# charger_schematic.net
KiCad netlist of a schematic drawn in Altium Designer
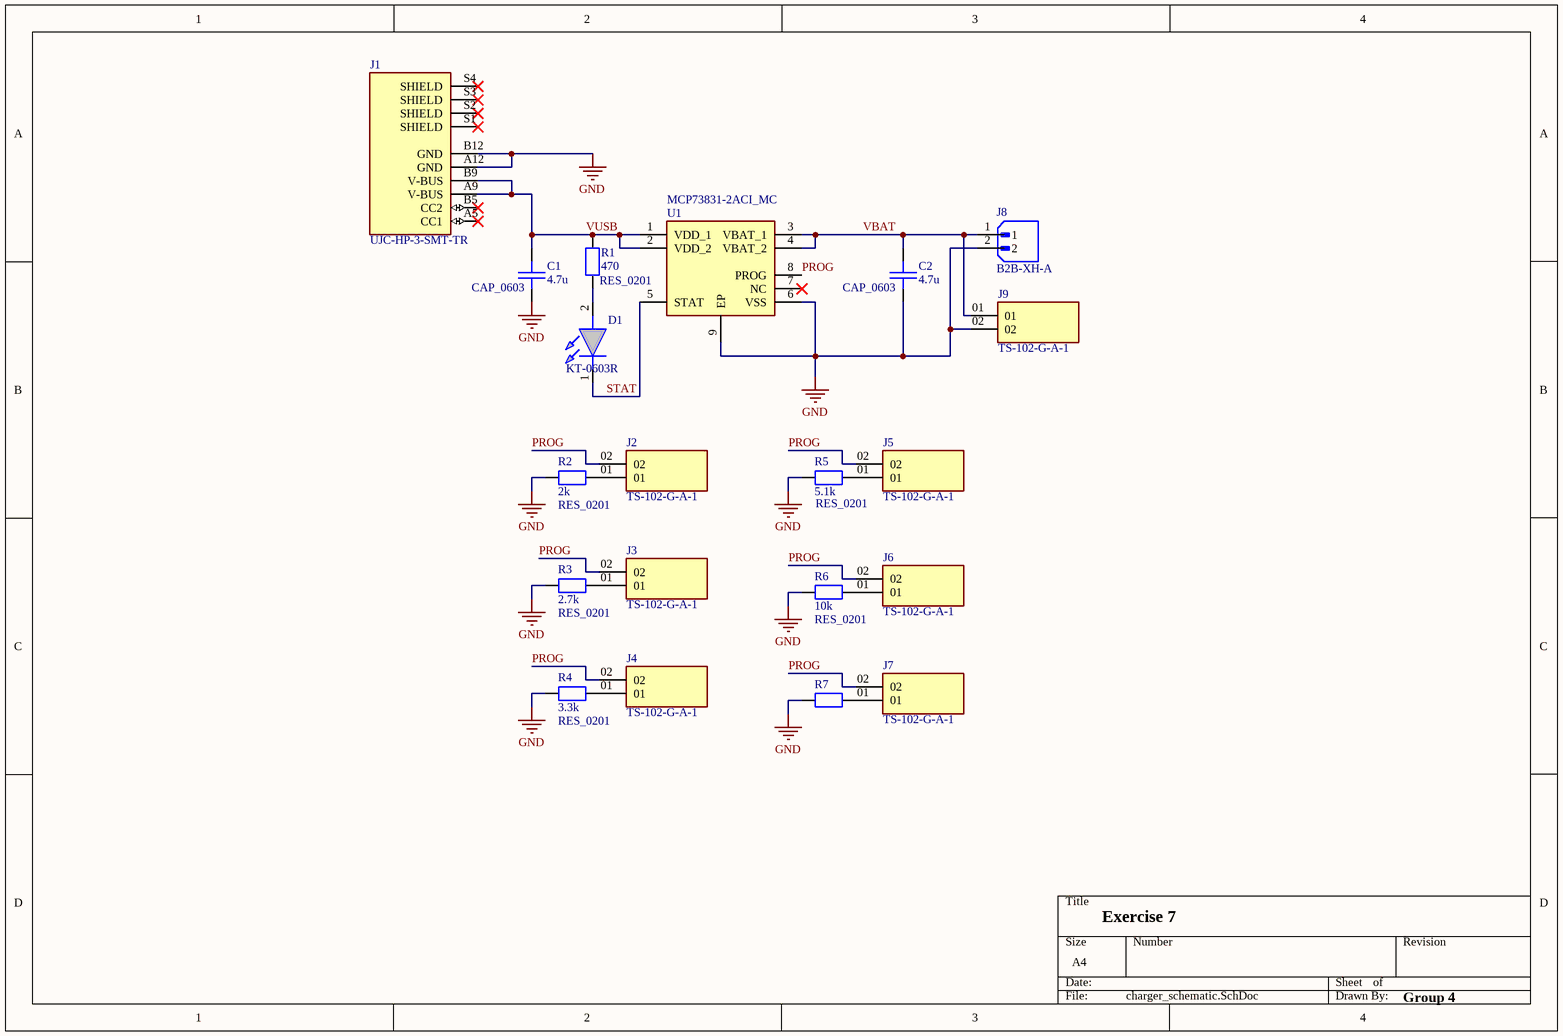
[diagram p0: charger_schematic.SchDoc]

(export (version "E")
  (design (tool "Eeschema 10.0.6"))
  (components
    (comp (ref "C1")
      (value "CAP_0603")
      (footprint "CAP_0603")
      (fields (field (name "ALTIUM_VALUE") "4.7u"))
      (libsource (lib "smd_sch_lib") (part "CAP_0603"))
    )
    (comp (ref "C2")
      (value "CAP_0603")
      (footprint "CAP_0603")
      (fields (field (name "ALTIUM_VALUE") "4.7u"))
      (libsource (lib "smd_sch_lib") (part "CAP_0603"))
    )
    (comp (ref "D1")
      (value "KT-0603R")
      (footprint "LEDC1608X70N")
      (description "Red 615~630nm 1.9~2.2V 0603 Light Emitting Diodes (LED) RoHS")
      (libsource (lib "LED_KT-0603R") (part "KT-0603R"))
    )
    (comp (ref "J1")
      (value "UJC-HP-3-SMT-TR")
      (footprint "CUI_UJC-HP-3-SMT-TR")
      (libsource (lib "UJC-HP-3-SMT-TR") (part "UJC-HP-3-SMT-TR"))
    )
    (comp (ref "J2")
      (value "TS-102-G-A-1")
      (footprint "SAMTEC_TS-102-G-A-1")
      (fields (field (name "MF") "{'manufacturer': u'Samtec Inc.'}"))
      (libsource (lib "TS-102-G-A-1") (part "TS-102-G-A-1"))
    )
    (comp (ref "J3")
      (value "TS-102-G-A-1")
      (footprint "SAMTEC_TS-102-G-A-1")
      (fields (field (name "MF") "{'manufacturer': u'Samtec Inc.'}"))
      (libsource (lib "TS-102-G-A-1") (part "TS-102-G-A-1"))
    )
    (comp (ref "J4")
      (value "TS-102-G-A-1")
      (footprint "SAMTEC_TS-102-G-A-1")
      (fields (field (name "MF") "{'manufacturer': u'Samtec Inc.'}"))
      (libsource (lib "TS-102-G-A-1") (part "TS-102-G-A-1"))
    )
    (comp (ref "J5")
      (value "TS-102-G-A-1")
      (footprint "SAMTEC_TS-102-G-A-1")
      (fields (field (name "MF") "{'manufacturer': u'Samtec Inc.'}"))
      (libsource (lib "TS-102-G-A-1") (part "TS-102-G-A-1"))
    )
    (comp (ref "J6")
      (value "TS-102-G-A-1")
      (footprint "SAMTEC_TS-102-G-A-1")
      (fields (field (name "MF") "{'manufacturer': u'Samtec Inc.'}"))
      (libsource (lib "TS-102-G-A-1") (part "TS-102-G-A-1"))
    )
    (comp (ref "J7")
      (value "TS-102-G-A-1")
      (footprint "SAMTEC_TS-102-G-A-1")
      (fields (field (name "MF") "{'manufacturer': u'Samtec Inc.'}"))
      (libsource (lib "TS-102-G-A-1") (part "TS-102-G-A-1"))
    )
    (comp (ref "J8")
      (value "B2B-XH-A")
      (footprint "JST_B2B-XH-A")
      (fields (field (name "MF") "{'manufacturer': u'JST Sales America Inc.'}"))
      (libsource (lib "B2B-XH-A") (part "B2B-XH-A"))
    )
    (comp (ref "J9")
      (value "TS-102-G-A-1")
      (footprint "SAMTEC_TS-102-G-A-1")
      (fields (field (name "MF") "{'manufacturer': u'Samtec Inc.'}"))
      (libsource (lib "") (part "TS-102-G-A-1_1"))
    )
    (comp (ref "R1")
      (value "RES_0201")
      (footprint "RES_0201")
      (fields (field (name "ALTIUM_VALUE") "470"))
      (libsource (lib "smd_sch_lib") (part "RES_0201"))
    )
    (comp (ref "R2")
      (value "RES_0201")
      (footprint "RES_0201")
      (fields (field (name "ALTIUM_VALUE") "2k"))
      (libsource (lib "smd_sch_lib") (part "RES_0201"))
    )
    (comp (ref "R3")
      (value "RES_0201")
      (footprint "RES_0201")
      (fields (field (name "ALTIUM_VALUE") "2.7k"))
      (libsource (lib "smd_sch_lib") (part "RES_0201"))
    )
    (comp (ref "R4")
      (value "RES_0201")
      (footprint "RES_0201")
      (fields (field (name "ALTIUM_VALUE") "3.3k"))
      (libsource (lib "smd_sch_lib") (part "RES_0201"))
    )
    (comp (ref "R5")
      (value "RES_0201")
      (footprint "RES_0201")
      (fields (field (name "ALTIUM_VALUE") "5.1k"))
      (libsource (lib "smd_sch_lib") (part "RES_0201"))
    )
    (comp (ref "R6")
      (value "RES_0201")
      (footprint "RES_0201")
      (fields (field (name "ALTIUM_VALUE") "10k"))
      (libsource (lib "smd_sch_lib") (part "RES_0201"))
    )
    (comp (ref "R7")
      (value "~")
      (footprint "PCBComponent_1")
      (libsource (lib "res_tht_sym_lib") (part "R_THT"))
    )
    (comp (ref "U1")
      (value "MCP73831-2ACI_MC")
      (footprint "SON50P300X200X100-9N-D")
      (description "Microchip MCP73831-2ACI/MC, Battery Charge Controller Lithium-Ion, Lithium-Polymer, 8-pin DFN")
      (fields
        (field (name "MANUFACTURER_PART_NUMBER") "MCP73831-2ACI/MC")
        (field (name "MOUSER PART NUMBER") "579-MCP73831-2ACI/MC")
      )
      (libsource (lib "MCP73831-2ACI_MC") (part "MCP73831-2ACI_MC"))
    )
  )
  (nets
    (net (code "1") (name "/PROG") (class "Default")
      (node (ref "J2") (pin "02") (pinfunction "02_02") (pintype "passive"))
      (node (ref "J3") (pin "02") (pinfunction "02_02") (pintype "passive"))
      (node (ref "J4") (pin "02") (pinfunction "02_02") (pintype "passive"))
      (node (ref "J5") (pin "02") (pinfunction "02_02") (pintype "passive"))
      (node (ref "J6") (pin "02") (pinfunction "02_02") (pintype "passive"))
      (node (ref "J7") (pin "02") (pinfunction "02_02") (pintype "passive"))
      (node (ref "U1") (pin "8") (pinfunction "PROG_8") (pintype "passive"))
    )
    (net (code "2") (name "/STAT") (class "Default")
      (node (ref "D1") (pin "1") (pinfunction "K_1") (pintype "passive"))
      (node (ref "U1") (pin "5") (pinfunction "STAT_5") (pintype "passive"))
    )
    (net (code "3") (name "/VBAT") (class "Default")
      (node (ref "C2") (pin "2") (pintype "passive"))
      (node (ref "J8") (pin "1") (pinfunction "1_1") (pintype "passive"))
      (node (ref "J9") (pin "01") (pinfunction "01_01") (pintype "passive"))
      (node (ref "U1") (pin "3") (pinfunction "VBAT_1_3") (pintype "passive"))
      (node (ref "U1") (pin "4") (pinfunction "VBAT_2_4") (pintype "passive"))
    )
    (net (code "4") (name "/VUSB") (class "Default")
      (node (ref "C1") (pin "2") (pintype "passive"))
      (node (ref "J1") (pin "A9") (pinfunction "V-BUS_A9") (pintype "power_in"))
      (node (ref "J1") (pin "B9") (pinfunction "V-BUS_B9") (pintype "power_in"))
      (node (ref "R1") (pin "2") (pintype "passive"))
      (node (ref "U1") (pin "1") (pinfunction "VDD_1_1") (pintype "passive"))
      (node (ref "U1") (pin "2") (pinfunction "VDD_2_2") (pintype "passive"))
    )
    (net (code "5") (name "GND") (class "Default")
      (node (ref "C1") (pin "1") (pintype "passive"))
      (node (ref "C2") (pin "1") (pintype "passive"))
      (node (ref "J1") (pin "A12") (pinfunction "GND_A12") (pintype "power_in"))
      (node (ref "J1") (pin "B12") (pinfunction "GND_B12") (pintype "power_in"))
      (node (ref "J8") (pin "2") (pinfunction "2_2") (pintype "passive"))
      (node (ref "J9") (pin "02") (pinfunction "02_02") (pintype "passive"))
      (node (ref "R2") (pin "2") (pintype "passive"))
      (node (ref "R3") (pin "2") (pintype "passive"))
      (node (ref "R4") (pin "2") (pintype "passive"))
      (node (ref "R5") (pin "2") (pintype "passive"))
      (node (ref "R6") (pin "2") (pintype "passive"))
      (node (ref "R7") (pin "2") (pinfunction "2_2") (pintype "passive"))
      (node (ref "U1") (pin "6") (pinfunction "VSS_6") (pintype "passive"))
      (node (ref "U1") (pin "9") (pinfunction "EP_9") (pintype "passive"))
    )
    (net (code "6") (name "Net-(D1-A)") (class "Default")
      (node (ref "D1") (pin "2") (pinfunction "A_2") (pintype "passive"))
      (node (ref "R1") (pin "1") (pintype "passive"))
    )
    (net (code "7") (name "Net-(J2-Pad01)") (class "Default")
      (node (ref "J2") (pin "01") (pinfunction "01_01") (pintype "passive"))
      (node (ref "R2") (pin "1") (pintype "passive"))
    )
    (net (code "8") (name "Net-(J3-Pad01)") (class "Default")
      (node (ref "J3") (pin "01") (pinfunction "01_01") (pintype "passive"))
      (node (ref "R3") (pin "1") (pintype "passive"))
    )
    (net (code "9") (name "Net-(J4-Pad01)") (class "Default")
      (node (ref "J4") (pin "01") (pinfunction "01_01") (pintype "passive"))
      (node (ref "R4") (pin "1") (pintype "passive"))
    )
    (net (code "10") (name "Net-(J5-Pad01)") (class "Default")
      (node (ref "J5") (pin "01") (pinfunction "01_01") (pintype "passive"))
      (node (ref "R5") (pin "1") (pintype "passive"))
    )
    (net (code "11") (name "Net-(J6-Pad01)") (class "Default")
      (node (ref "J6") (pin "01") (pinfunction "01_01") (pintype "passive"))
      (node (ref "R6") (pin "1") (pintype "passive"))
    )
    (net (code "12") (name "Net-(J7-Pad01)") (class "Default")
      (node (ref "J7") (pin "01") (pinfunction "01_01") (pintype "passive"))
      (node (ref "R7") (pin "1") (pinfunction "1_1") (pintype "passive"))
    )
    (net (code "13") (name "unconnected-(J1-CC1-PadA5)") (class "Default")
      (node (ref "J1") (pin "A5") (pinfunction "CC1_A5") (pintype "bidirectional+no_connect"))
    )
    (net (code "14") (name "unconnected-(J1-CC2-PadB5)") (class "Default")
      (node (ref "J1") (pin "B5") (pinfunction "CC2_B5") (pintype "bidirectional+no_connect"))
    )
    (net (code "15") (name "unconnected-(J1-SHIELD-PadS1)") (class "Default")
      (node (ref "J1") (pin "S1") (pinfunction "SHIELD_S1") (pintype "passive+no_connect"))
    )
    (net (code "16") (name "unconnected-(J1-SHIELD-PadS2)") (class "Default")
      (node (ref "J1") (pin "S2") (pinfunction "SHIELD_S2") (pintype "passive+no_connect"))
    )
    (net (code "17") (name "unconnected-(J1-SHIELD-PadS3)") (class "Default")
      (node (ref "J1") (pin "S3") (pinfunction "SHIELD_S3") (pintype "passive+no_connect"))
    )
    (net (code "18") (name "unconnected-(J1-SHIELD-PadS4)") (class "Default")
      (node (ref "J1") (pin "S4") (pinfunction "SHIELD_S4") (pintype "passive+no_connect"))
    )
    (net (code "19") (name "unconnected-(U1-NC-Pad7)") (class "Default")
      (node (ref "U1") (pin "7") (pinfunction "NC_7") (pintype "passive+no_connect"))
    )
  )
)
